# DRV8303.net
KiCad netlist of a schematic drawn in Altium Designer
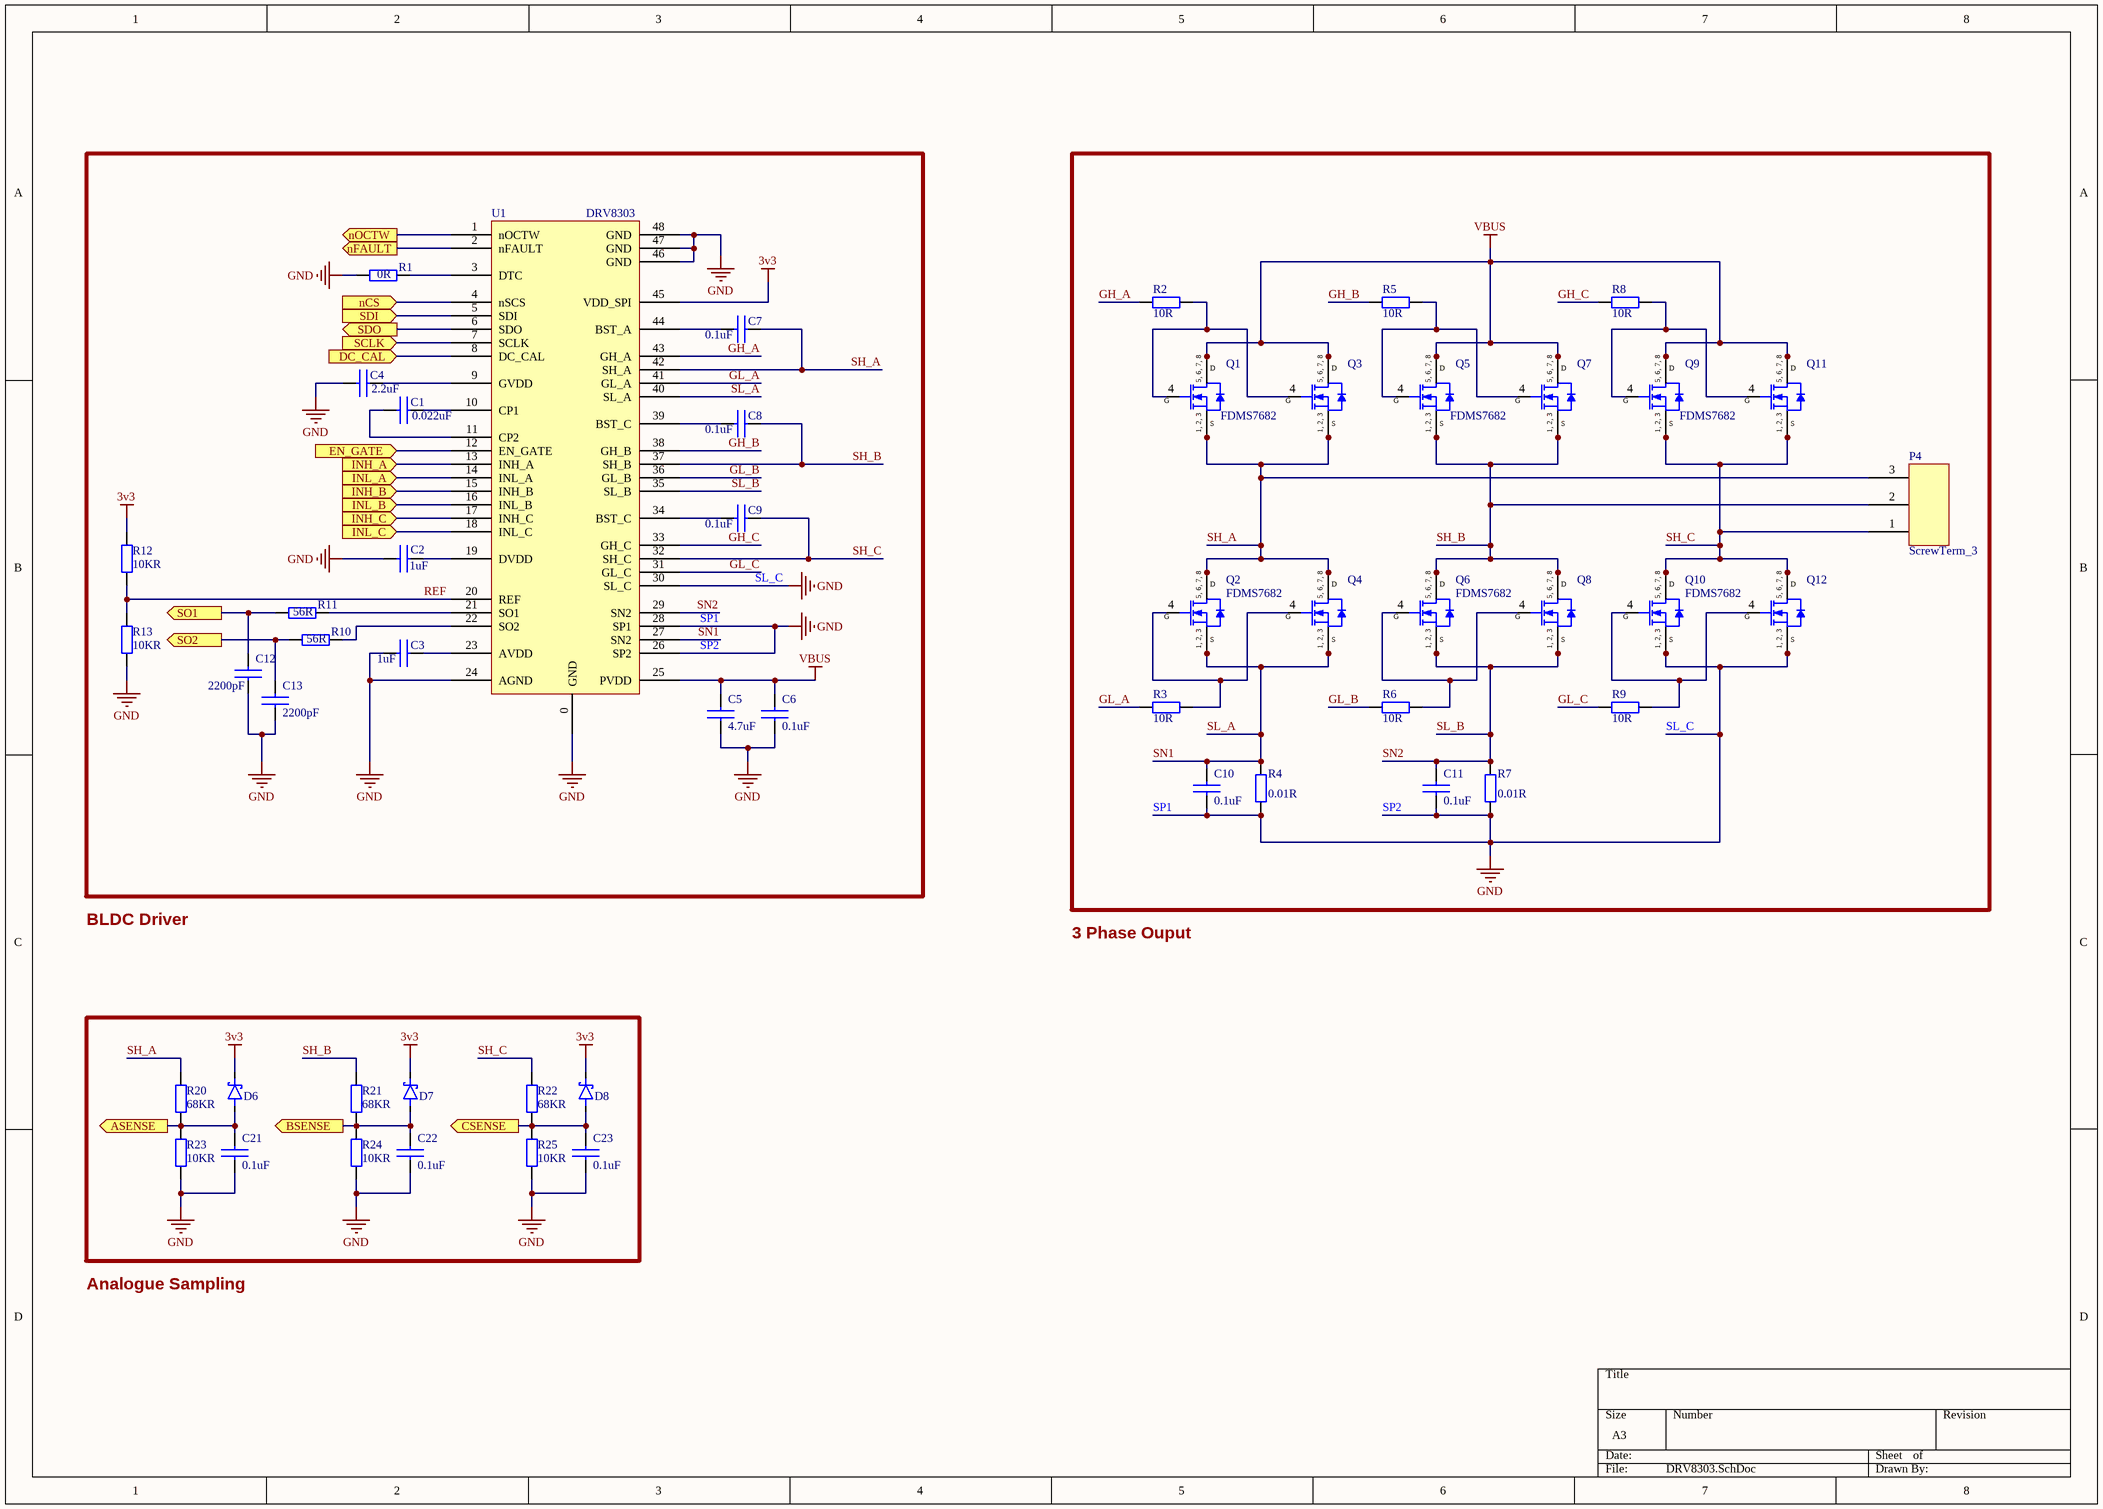
[diagram p0: DRV8303.SchDoc]

(export (version "E")
  (design (tool "Eeschema 10.0.6"))
  (components
    (comp (ref "C1")
      (value "0.022uF")
      (footprint "RESC0603(1608)_N")
      (description "Non polarized capacitor")
      (libsource (lib "myPassives") (part "Capacitor"))
    )
    (comp (ref "C2")
      (value "1uF")
      (footprint "RESC0603(1608)_N")
      (description "Non polarized capacitor")
      (libsource (lib "myPassives") (part "Capacitor"))
    )
    (comp (ref "C3")
      (value "1uF")
      (footprint "RESC0603(1608)_N")
      (description "Non polarized capacitor")
      (libsource (lib "myPassives") (part "Capacitor"))
    )
    (comp (ref "C4")
      (value "2.2uF")
      (footprint "RESC0603(1608)_N")
      (description "Non polarized capacitor")
      (libsource (lib "myPassives") (part "Capacitor"))
    )
    (comp (ref "C5")
      (value "4.7uF")
      (footprint "RESC0603(1608)_N")
      (description "Non polarized capacitor")
      (libsource (lib "myPassives") (part "Capacitor"))
    )
    (comp (ref "C6")
      (value "0.1uF")
      (footprint "RESC0603(1608)_N")
      (description "Non polarized capacitor")
      (libsource (lib "myPassives") (part "Capacitor"))
    )
    (comp (ref "C7")
      (value "0.1uF")
      (footprint "RESC0603(1608)_N")
      (description "Non polarized capacitor")
      (libsource (lib "myPassives") (part "Capacitor"))
    )
    (comp (ref "C8")
      (value "0.1uF")
      (footprint "RESC0603(1608)_N")
      (description "Non polarized capacitor")
      (libsource (lib "myPassives") (part "Capacitor"))
    )
    (comp (ref "C9")
      (value "0.1uF")
      (footprint "RESC0603(1608)_N")
      (description "Non polarized capacitor")
      (libsource (lib "myPassives") (part "Capacitor"))
    )
    (comp (ref "C10")
      (value "0.1uF")
      (footprint "RESC0603(1608)_N")
      (description "Non polarized capacitor")
      (libsource (lib "myPassives") (part "Capacitor"))
    )
    (comp (ref "C11")
      (value "0.1uF")
      (footprint "RESC0603(1608)_N")
      (description "Non polarized capacitor")
      (libsource (lib "myPassives") (part "Capacitor"))
    )
    (comp (ref "C12")
      (value "2200pF")
      (footprint "RESC0603(1608)_N")
      (description "Non polarized capacitor")
      (libsource (lib "myPassives") (part "Capacitor"))
    )
    (comp (ref "C13")
      (value "2200pF")
      (footprint "RESC0603(1608)_N")
      (description "Non polarized capacitor")
      (libsource (lib "myPassives") (part "Capacitor"))
    )
    (comp (ref "C21")
      (value "0.1uF")
      (footprint "RESC0603(1608)_N")
      (description "Non polarized capacitor")
      (libsource (lib "myPassives") (part "Capacitor"))
    )
    (comp (ref "C22")
      (value "0.1uF")
      (footprint "RESC0603(1608)_N")
      (description "Non polarized capacitor")
      (libsource (lib "myPassives") (part "Capacitor"))
    )
    (comp (ref "C23")
      (value "0.1uF")
      (footprint "RESC0603(1608)_N")
      (description "Non polarized capacitor")
      (libsource (lib "myPassives") (part "Capacitor"))
    )
    (comp (ref "D6")
      (value "Diode_schottky")
      (footprint "SOD523")
      (libsource (lib "myPassives") (part "Diode_schottky"))
    )
    (comp (ref "D7")
      (value "Diode_schottky")
      (footprint "SOD523")
      (libsource (lib "myPassives") (part "Diode_schottky"))
    )
    (comp (ref "D8")
      (value "Diode_schottky")
      (footprint "SOD523")
      (libsource (lib "myPassives") (part "Diode_schottky"))
    )
    (comp (ref "P4")
      (value "ScrewTerm_3")
      (footprint "ScrewTerm_3")
      (libsource (lib "Seeed") (part "ScrewTerm_3"))
    )
    (comp (ref "Q1") (value "FDMS7682") (footprint "PQFN8_5x6") (libsource (lib "myLibs") (part "FDMS7682")))
    (comp (ref "Q2") (value "FDMS7682") (footprint "PQFN8_5x6") (libsource (lib "myLibs") (part "FDMS7682")))
    (comp (ref "Q3") (value "FDMS7682") (footprint "PQFN8_5x6") (libsource (lib "myLibs") (part "FDMS7682")))
    (comp (ref "Q4") (value "FDMS7682") (footprint "PQFN8_5x6") (libsource (lib "myLibs") (part "FDMS7682")))
    (comp (ref "Q5") (value "FDMS7682") (footprint "PQFN8_5x6") (libsource (lib "myLibs") (part "FDMS7682")))
    (comp (ref "Q6") (value "FDMS7682") (footprint "PQFN8_5x6") (libsource (lib "myLibs") (part "FDMS7682")))
    (comp (ref "Q7") (value "FDMS7682") (footprint "PQFN8_5x6") (libsource (lib "myLibs") (part "FDMS7682")))
    (comp (ref "Q8") (value "FDMS7682") (footprint "PQFN8_5x6") (libsource (lib "myLibs") (part "FDMS7682")))
    (comp (ref "Q9") (value "FDMS7682") (footprint "PQFN8_5x6") (libsource (lib "myLibs") (part "FDMS7682")))
    (comp (ref "Q10") (value "FDMS7682") (footprint "PQFN8_5x6") (libsource (lib "myLibs") (part "FDMS7682")))
    (comp (ref "Q11") (value "FDMS7682") (footprint "PQFN8_5x6") (libsource (lib "myLibs") (part "FDMS7682")))
    (comp (ref "Q12") (value "FDMS7682") (footprint "PQFN8_5x6") (libsource (lib "myLibs") (part "FDMS7682")))
    (comp (ref "R1")
      (value "0R")
      (footprint "RESC0603(1608)_N")
      (description "Resistor")
      (libsource (lib "") (part "Resistor_2"))
    )
    (comp (ref "R2")
      (value "10R")
      (footprint "RESC0603(1608)_N")
      (description "Resistor")
      (libsource (lib "") (part "Resistor_2"))
    )
    (comp (ref "R3")
      (value "10R")
      (footprint "RESC0603(1608)_N")
      (description "Resistor")
      (libsource (lib "") (part "Resistor_2"))
    )
    (comp (ref "R4")
      (value "0.01R")
      (footprint "RESC1206(3216)_M")
      (description "Resistor")
      (libsource (lib "myPassives") (part "Resistor"))
    )
    (comp (ref "R5")
      (value "10R")
      (footprint "RESC0603(1608)_N")
      (description "Resistor")
      (libsource (lib "") (part "Resistor_2"))
    )
    (comp (ref "R6")
      (value "10R")
      (footprint "RESC0603(1608)_N")
      (description "Resistor")
      (libsource (lib "") (part "Resistor_2"))
    )
    (comp (ref "R7")
      (value "0.01R")
      (footprint "RESC1206(3216)_M")
      (description "Resistor")
      (libsource (lib "myPassives") (part "Resistor"))
    )
    (comp (ref "R8")
      (value "10R")
      (footprint "RESC0603(1608)_N")
      (description "Resistor")
      (libsource (lib "") (part "Resistor_2"))
    )
    (comp (ref "R9")
      (value "10R")
      (footprint "RESC0603(1608)_N")
      (description "Resistor")
      (libsource (lib "") (part "Resistor_2"))
    )
    (comp (ref "R10")
      (value "56R")
      (footprint "RESC0603(1608)_N")
      (description "Resistor")
      (libsource (lib "") (part "Resistor_2"))
    )
    (comp (ref "R11")
      (value "56R")
      (footprint "RESC0603(1608)_N")
      (description "Resistor")
      (libsource (lib "") (part "Resistor_2"))
    )
    (comp (ref "R12")
      (value "10KR")
      (footprint "RESC0603(1608)_N")
      (description "Resistor")
      (libsource (lib "") (part "Resistor_1"))
    )
    (comp (ref "R13")
      (value "10KR")
      (footprint "RESC0603(1608)_N")
      (description "Resistor")
      (libsource (lib "") (part "Resistor_1"))
    )
    (comp (ref "R20")
      (value "68KR")
      (footprint "RESC0603(1608)_N")
      (description "Resistor")
      (libsource (lib "") (part "Resistor_1"))
    )
    (comp (ref "R21")
      (value "68KR")
      (footprint "RESC0603(1608)_N")
      (description "Resistor")
      (libsource (lib "") (part "Resistor_1"))
    )
    (comp (ref "R22")
      (value "68KR")
      (footprint "RESC0603(1608)_N")
      (description "Resistor")
      (libsource (lib "") (part "Resistor_1"))
    )
    (comp (ref "R23")
      (value "10KR")
      (footprint "RESC0603(1608)_N")
      (description "Resistor")
      (libsource (lib "") (part "Resistor_1"))
    )
    (comp (ref "R24")
      (value "10KR")
      (footprint "RESC0603(1608)_N")
      (description "Resistor")
      (libsource (lib "") (part "Resistor_1"))
    )
    (comp (ref "R25")
      (value "10KR")
      (footprint "RESC0603(1608)_N")
      (description "Resistor")
      (libsource (lib "") (part "Resistor_1"))
    )
    (comp (ref "U1") (value "DRV8303") (footprint "HSSOP48") (libsource (lib "myLibs") (part "DRV8303")))
  )
  (nets
    (net (code "1") (name "/ASENSE") (class "Default")
      (node (ref "C21") (pin "1") (pintype "passive"))
      (node (ref "D6") (pin "2") (pintype "passive"))
      (node (ref "R20") (pin "1") (pintype "passive"))
      (node (ref "R23") (pin "2") (pintype "passive"))
    )
    (net (code "2") (name "/BSENSE") (class "Default")
      (node (ref "C22") (pin "1") (pintype "passive"))
      (node (ref "D7") (pin "2") (pintype "passive"))
      (node (ref "R21") (pin "1") (pintype "passive"))
      (node (ref "R24") (pin "2") (pintype "passive"))
    )
    (net (code "3") (name "/CSENSE") (class "Default")
      (node (ref "C23") (pin "1") (pintype "passive"))
      (node (ref "D8") (pin "2") (pintype "passive"))
      (node (ref "R22") (pin "1") (pintype "passive"))
      (node (ref "R25") (pin "2") (pintype "passive"))
    )
    (net (code "4") (name "/DC_CAL") (class "Default")
      (node (ref "U1") (pin "8") (pinfunction "DC_CAL_8") (pintype "passive"))
    )
    (net (code "5") (name "/EN_GATE") (class "Default")
      (node (ref "U1") (pin "12") (pinfunction "EN_GATE_12") (pintype "passive"))
    )
    (net (code "6") (name "/GH_A") (class "Default")
      (node (ref "R2") (pin "1") (pintype "passive"))
      (node (ref "U1") (pin "43") (pinfunction "GH_A_43") (pintype "passive"))
    )
    (net (code "7") (name "/GH_B") (class "Default")
      (node (ref "R5") (pin "1") (pintype "passive"))
      (node (ref "U1") (pin "38") (pinfunction "GH_B_38") (pintype "passive"))
    )
    (net (code "8") (name "/GH_C") (class "Default")
      (node (ref "R8") (pin "1") (pintype "passive"))
      (node (ref "U1") (pin "33") (pinfunction "GH_C_33") (pintype "passive"))
    )
    (net (code "9") (name "/GL_A") (class "Default")
      (node (ref "R3") (pin "1") (pintype "passive"))
      (node (ref "U1") (pin "41") (pinfunction "GL_A_41") (pintype "passive"))
    )
    (net (code "10") (name "/GL_B") (class "Default")
      (node (ref "R6") (pin "1") (pintype "passive"))
      (node (ref "U1") (pin "36") (pinfunction "GL_B_36") (pintype "passive"))
    )
    (net (code "11") (name "/GL_C") (class "Default")
      (node (ref "R9") (pin "1") (pintype "passive"))
      (node (ref "U1") (pin "31") (pinfunction "GL_C_31") (pintype "passive"))
    )
    (net (code "12") (name "/INH_A") (class "Default")
      (node (ref "U1") (pin "13") (pinfunction "INH_A_13") (pintype "passive"))
    )
    (net (code "13") (name "/INH_B") (class "Default")
      (node (ref "U1") (pin "15") (pinfunction "INH_B_15") (pintype "passive"))
    )
    (net (code "14") (name "/INH_C") (class "Default")
      (node (ref "U1") (pin "17") (pinfunction "INH_C_17") (pintype "passive"))
    )
    (net (code "15") (name "/INL_A") (class "Default")
      (node (ref "U1") (pin "14") (pinfunction "INL_A_14") (pintype "passive"))
    )
    (net (code "16") (name "/INL_B") (class "Default")
      (node (ref "U1") (pin "16") (pinfunction "INL_B_16") (pintype "passive"))
    )
    (net (code "17") (name "/INL_C") (class "Default")
      (node (ref "U1") (pin "18") (pinfunction "INL_C_18") (pintype "passive"))
    )
    (net (code "18") (name "/REF") (class "Default")
      (node (ref "R12") (pin "1") (pintype "passive"))
      (node (ref "R13") (pin "2") (pintype "passive"))
      (node (ref "U1") (pin "20") (pinfunction "REF_20") (pintype "passive"))
    )
    (net (code "19") (name "/SCLK") (class "Default")
      (node (ref "U1") (pin "7") (pinfunction "SCLK_7") (pintype "passive"))
    )
    (net (code "20") (name "/SDI") (class "Default")
      (node (ref "U1") (pin "5") (pinfunction "SDI_5") (pintype "passive"))
    )
    (net (code "21") (name "/SDO") (class "Default")
      (node (ref "U1") (pin "6") (pinfunction "SDO_6") (pintype "passive"))
    )
    (net (code "22") (name "/SH_A") (class "Default")
      (node (ref "C7") (pin "2") (pintype "passive"))
      (node (ref "P4") (pin "3") (pintype "passive"))
      (node (ref "Q1") (pin "1") (pinfunction "S_1") (pintype "passive"))
      (node (ref "Q1") (pin "2") (pinfunction "S_2") (pintype "power_in"))
      (node (ref "Q1") (pin "3") (pinfunction "S_3") (pintype "power_in"))
      (node (ref "Q2") (pin "0") (pinfunction "D_0") (pintype "passive"))
      (node (ref "Q2") (pin "5") (pinfunction "D_5") (pintype "passive"))
      (node (ref "Q2") (pin "6") (pinfunction "D_6") (pintype "passive"))
      (node (ref "Q2") (pin "7") (pinfunction "D_7") (pintype "passive"))
      (node (ref "Q2") (pin "8") (pinfunction "D_8") (pintype "passive"))
      (node (ref "Q3") (pin "1") (pinfunction "S_1") (pintype "passive"))
      (node (ref "Q3") (pin "2") (pinfunction "S_2") (pintype "power_in"))
      (node (ref "Q3") (pin "3") (pinfunction "S_3") (pintype "power_in"))
      (node (ref "Q4") (pin "0") (pinfunction "D_0") (pintype "passive"))
      (node (ref "Q4") (pin "5") (pinfunction "D_5") (pintype "passive"))
      (node (ref "Q4") (pin "6") (pinfunction "D_6") (pintype "passive"))
      (node (ref "Q4") (pin "7") (pinfunction "D_7") (pintype "passive"))
      (node (ref "Q4") (pin "8") (pinfunction "D_8") (pintype "passive"))
      (node (ref "R20") (pin "2") (pintype "passive"))
      (node (ref "U1") (pin "42") (pinfunction "SH_A_42") (pintype "passive"))
    )
    (net (code "23") (name "/SH_B") (class "Default")
      (node (ref "C8") (pin "2") (pintype "passive"))
      (node (ref "P4") (pin "2") (pintype "passive"))
      (node (ref "Q5") (pin "1") (pinfunction "S_1") (pintype "passive"))
      (node (ref "Q5") (pin "2") (pinfunction "S_2") (pintype "power_in"))
      (node (ref "Q5") (pin "3") (pinfunction "S_3") (pintype "power_in"))
      (node (ref "Q6") (pin "0") (pinfunction "D_0") (pintype "passive"))
      (node (ref "Q6") (pin "5") (pinfunction "D_5") (pintype "passive"))
      (node (ref "Q6") (pin "6") (pinfunction "D_6") (pintype "passive"))
      (node (ref "Q6") (pin "7") (pinfunction "D_7") (pintype "passive"))
      (node (ref "Q6") (pin "8") (pinfunction "D_8") (pintype "passive"))
      (node (ref "Q7") (pin "1") (pinfunction "S_1") (pintype "passive"))
      (node (ref "Q7") (pin "2") (pinfunction "S_2") (pintype "power_in"))
      (node (ref "Q7") (pin "3") (pinfunction "S_3") (pintype "power_in"))
      (node (ref "Q8") (pin "0") (pinfunction "D_0") (pintype "passive"))
      (node (ref "Q8") (pin "5") (pinfunction "D_5") (pintype "passive"))
      (node (ref "Q8") (pin "6") (pinfunction "D_6") (pintype "passive"))
      (node (ref "Q8") (pin "7") (pinfunction "D_7") (pintype "passive"))
      (node (ref "Q8") (pin "8") (pinfunction "D_8") (pintype "passive"))
      (node (ref "R21") (pin "2") (pintype "passive"))
      (node (ref "U1") (pin "37") (pinfunction "SH_B_37") (pintype "passive"))
    )
    (net (code "24") (name "/SH_C") (class "Default")
      (node (ref "C9") (pin "2") (pintype "passive"))
      (node (ref "P4") (pin "1") (pintype "passive"))
      (node (ref "Q10") (pin "0") (pinfunction "D_0") (pintype "passive"))
      (node (ref "Q10") (pin "5") (pinfunction "D_5") (pintype "passive"))
      (node (ref "Q10") (pin "6") (pinfunction "D_6") (pintype "passive"))
      (node (ref "Q10") (pin "7") (pinfunction "D_7") (pintype "passive"))
      (node (ref "Q10") (pin "8") (pinfunction "D_8") (pintype "passive"))
      (node (ref "Q11") (pin "1") (pinfunction "S_1") (pintype "passive"))
      (node (ref "Q11") (pin "2") (pinfunction "S_2") (pintype "power_in"))
      (node (ref "Q11") (pin "3") (pinfunction "S_3") (pintype "power_in"))
      (node (ref "Q12") (pin "0") (pinfunction "D_0") (pintype "passive"))
      (node (ref "Q12") (pin "5") (pinfunction "D_5") (pintype "passive"))
      (node (ref "Q12") (pin "6") (pinfunction "D_6") (pintype "passive"))
      (node (ref "Q12") (pin "7") (pinfunction "D_7") (pintype "passive"))
      (node (ref "Q12") (pin "8") (pinfunction "D_8") (pintype "passive"))
      (node (ref "Q9") (pin "1") (pinfunction "S_1") (pintype "passive"))
      (node (ref "Q9") (pin "2") (pinfunction "S_2") (pintype "power_in"))
      (node (ref "Q9") (pin "3") (pinfunction "S_3") (pintype "power_in"))
      (node (ref "R22") (pin "2") (pintype "passive"))
      (node (ref "U1") (pin "32") (pinfunction "SH_C_32") (pintype "passive"))
    )
    (net (code "25") (name "/SL_A") (class "Default")
      (node (ref "C10") (pin "1") (pintype "passive"))
      (node (ref "Q2") (pin "1") (pinfunction "S_1") (pintype "passive"))
      (node (ref "Q2") (pin "2") (pinfunction "S_2") (pintype "power_in"))
      (node (ref "Q2") (pin "3") (pinfunction "S_3") (pintype "power_in"))
      (node (ref "Q4") (pin "1") (pinfunction "S_1") (pintype "passive"))
      (node (ref "Q4") (pin "2") (pinfunction "S_2") (pintype "power_in"))
      (node (ref "Q4") (pin "3") (pinfunction "S_3") (pintype "power_in"))
      (node (ref "R4") (pin "1") (pintype "passive"))
      (node (ref "U1") (pin "27") (pinfunction "SN2_27") (pintype "passive"))
      (node (ref "U1") (pin "40") (pinfunction "SL_A_40") (pintype "passive"))
    )
    (net (code "26") (name "/SL_B") (class "Default")
      (node (ref "C11") (pin "1") (pintype "passive"))
      (node (ref "Q6") (pin "1") (pinfunction "S_1") (pintype "passive"))
      (node (ref "Q6") (pin "2") (pinfunction "S_2") (pintype "power_in"))
      (node (ref "Q6") (pin "3") (pinfunction "S_3") (pintype "power_in"))
      (node (ref "Q8") (pin "1") (pinfunction "S_1") (pintype "passive"))
      (node (ref "Q8") (pin "2") (pinfunction "S_2") (pintype "power_in"))
      (node (ref "Q8") (pin "3") (pinfunction "S_3") (pintype "power_in"))
      (node (ref "R7") (pin "1") (pintype "passive"))
      (node (ref "U1") (pin "29") (pinfunction "SN2_29") (pintype "passive"))
      (node (ref "U1") (pin "35") (pinfunction "SL_B_35") (pintype "passive"))
    )
    (net (code "27") (name "/SO1") (class "Default")
      (node (ref "C12") (pin "1") (pintype "passive"))
      (node (ref "R11") (pin "1") (pintype "passive"))
    )
    (net (code "28") (name "/SO2") (class "Default")
      (node (ref "C13") (pin "1") (pintype "passive"))
      (node (ref "R10") (pin "1") (pintype "passive"))
    )
    (net (code "29") (name "/nCS") (class "Default")
      (node (ref "U1") (pin "4") (pinfunction "nSCS_4") (pintype "passive"))
    )
    (net (code "30") (name "/nFAULT") (class "Default")
      (node (ref "U1") (pin "2") (pinfunction "nFAULT_2") (pintype "passive"))
    )
    (net (code "31") (name "/nOCTW") (class "Default")
      (node (ref "U1") (pin "1") (pinfunction "nOCTW_1") (pintype "passive"))
    )
    (net (code "32") (name "3v3") (class "Default")
      (node (ref "D6") (pin "1") (pintype "passive"))
      (node (ref "D7") (pin "1") (pintype "passive"))
      (node (ref "D8") (pin "1") (pintype "passive"))
      (node (ref "R12") (pin "2") (pintype "passive"))
      (node (ref "U1") (pin "45") (pinfunction "VDD_SPI_45") (pintype "passive"))
    )
    (net (code "33") (name "GND") (class "Default")
      (node (ref "C10") (pin "2") (pintype "passive"))
      (node (ref "C11") (pin "2") (pintype "passive"))
      (node (ref "C12") (pin "2") (pintype "passive"))
      (node (ref "C13") (pin "2") (pintype "passive"))
      (node (ref "C2") (pin "1") (pintype "passive"))
      (node (ref "C21") (pin "2") (pintype "passive"))
      (node (ref "C22") (pin "2") (pintype "passive"))
      (node (ref "C23") (pin "2") (pintype "passive"))
      (node (ref "C3") (pin "1") (pintype "passive"))
      (node (ref "C4") (pin "1") (pintype "passive"))
      (node (ref "C5") (pin "2") (pintype "passive"))
      (node (ref "C6") (pin "2") (pintype "passive"))
      (node (ref "Q10") (pin "1") (pinfunction "S_1") (pintype "passive"))
      (node (ref "Q10") (pin "2") (pinfunction "S_2") (pintype "power_in"))
      (node (ref "Q10") (pin "3") (pinfunction "S_3") (pintype "power_in"))
      (node (ref "Q12") (pin "1") (pinfunction "S_1") (pintype "passive"))
      (node (ref "Q12") (pin "2") (pinfunction "S_2") (pintype "power_in"))
      (node (ref "Q12") (pin "3") (pinfunction "S_3") (pintype "power_in"))
      (node (ref "R1") (pin "1") (pintype "passive"))
      (node (ref "R13") (pin "1") (pintype "passive"))
      (node (ref "R23") (pin "1") (pintype "passive"))
      (node (ref "R24") (pin "1") (pintype "passive"))
      (node (ref "R25") (pin "1") (pintype "passive"))
      (node (ref "R4") (pin "2") (pintype "passive"))
      (node (ref "R7") (pin "2") (pintype "passive"))
      (node (ref "U1") (pin "0") (pinfunction "GND_0") (pintype "passive"))
      (node (ref "U1") (pin "24") (pinfunction "AGND_24") (pintype "passive"))
      (node (ref "U1") (pin "26") (pinfunction "SP2_26") (pintype "passive"))
      (node (ref "U1") (pin "28") (pinfunction "SP1_28") (pintype "passive"))
      (node (ref "U1") (pin "30") (pinfunction "SL_C_30") (pintype "passive"))
      (node (ref "U1") (pin "46") (pinfunction "GND_46") (pintype "passive"))
      (node (ref "U1") (pin "47") (pinfunction "GND_47") (pintype "passive"))
      (node (ref "U1") (pin "48") (pinfunction "GND_48") (pintype "passive"))
    )
    (net (code "34") (name "Net-(C8-Pad1)") (class "Default")
      (node (ref "C8") (pin "1") (pintype "passive"))
      (node (ref "U1") (pin "39") (pinfunction "BST_C_39") (pintype "passive"))
    )
    (net (code "35") (name "Net-(C9-Pad1)") (class "Default")
      (node (ref "C9") (pin "1") (pintype "passive"))
      (node (ref "U1") (pin "34") (pinfunction "BST_C_34") (pintype "passive"))
    )
    (net (code "36") (name "Net-(Q1-G)") (class "Default")
      (node (ref "Q1") (pin "4") (pinfunction "G_4") (pintype "passive"))
      (node (ref "Q3") (pin "4") (pinfunction "G_4") (pintype "passive"))
      (node (ref "R2") (pin "2") (pintype "passive"))
    )
    (net (code "37") (name "Net-(Q2-G)") (class "Default")
      (node (ref "Q2") (pin "4") (pinfunction "G_4") (pintype "passive"))
      (node (ref "Q4") (pin "4") (pinfunction "G_4") (pintype "passive"))
      (node (ref "R3") (pin "2") (pintype "passive"))
    )
    (net (code "38") (name "Net-(Q5-G)") (class "Default")
      (node (ref "Q5") (pin "4") (pinfunction "G_4") (pintype "passive"))
      (node (ref "Q7") (pin "4") (pinfunction "G_4") (pintype "passive"))
      (node (ref "R5") (pin "2") (pintype "passive"))
    )
    (net (code "39") (name "Net-(Q6-G)") (class "Default")
      (node (ref "Q6") (pin "4") (pinfunction "G_4") (pintype "passive"))
      (node (ref "Q8") (pin "4") (pinfunction "G_4") (pintype "passive"))
      (node (ref "R6") (pin "2") (pintype "passive"))
    )
    (net (code "40") (name "Net-(Q10-G)") (class "Default")
      (node (ref "Q10") (pin "4") (pinfunction "G_4") (pintype "passive"))
      (node (ref "Q12") (pin "4") (pinfunction "G_4") (pintype "passive"))
      (node (ref "R9") (pin "2") (pintype "passive"))
    )
    (net (code "41") (name "Net-(Q11-G)") (class "Default")
      (node (ref "Q11") (pin "4") (pinfunction "G_4") (pintype "passive"))
      (node (ref "Q9") (pin "4") (pinfunction "G_4") (pintype "passive"))
      (node (ref "R8") (pin "2") (pintype "passive"))
    )
    (net (code "42") (name "Net-(U1-AVDD)") (class "Default")
      (node (ref "C3") (pin "2") (pintype "passive"))
      (node (ref "U1") (pin "23") (pinfunction "AVDD_23") (pintype "passive"))
    )
    (net (code "43") (name "Net-(U1-BST_A)") (class "Default")
      (node (ref "C7") (pin "1") (pintype "passive"))
      (node (ref "U1") (pin "44") (pinfunction "BST_A_44") (pintype "passive"))
    )
    (net (code "44") (name "Net-(U1-CP1)") (class "Default")
      (node (ref "C1") (pin "2") (pintype "passive"))
      (node (ref "U1") (pin "10") (pinfunction "CP1_10") (pintype "passive"))
    )
    (net (code "45") (name "Net-(U1-CP2)") (class "Default")
      (node (ref "C1") (pin "1") (pintype "passive"))
      (node (ref "U1") (pin "11") (pinfunction "CP2_11") (pintype "passive"))
    )
    (net (code "46") (name "Net-(U1-DTC)") (class "Default")
      (node (ref "R1") (pin "2") (pintype "passive"))
      (node (ref "U1") (pin "3") (pinfunction "DTC_3") (pintype "passive"))
    )
    (net (code "47") (name "Net-(U1-DVDD)") (class "Default")
      (node (ref "C2") (pin "2") (pintype "passive"))
      (node (ref "U1") (pin "19") (pinfunction "DVDD_19") (pintype "passive"))
    )
    (net (code "48") (name "Net-(U1-GVDD)") (class "Default")
      (node (ref "C4") (pin "2") (pintype "passive"))
      (node (ref "U1") (pin "9") (pinfunction "GVDD_9") (pintype "passive"))
    )
    (net (code "49") (name "Net-(U1-SO1)") (class "Default")
      (node (ref "R11") (pin "2") (pintype "passive"))
      (node (ref "U1") (pin "21") (pinfunction "SO1_21") (pintype "passive"))
    )
    (net (code "50") (name "Net-(U1-SO2)") (class "Default")
      (node (ref "R10") (pin "2") (pintype "passive"))
      (node (ref "U1") (pin "22") (pinfunction "SO2_22") (pintype "passive"))
    )
    (net (code "51") (name "VBUS") (class "Default")
      (node (ref "C5") (pin "1") (pintype "passive"))
      (node (ref "C6") (pin "1") (pintype "passive"))
      (node (ref "Q1") (pin "0") (pinfunction "D_0") (pintype "passive"))
      (node (ref "Q1") (pin "5") (pinfunction "D_5") (pintype "passive"))
      (node (ref "Q1") (pin "6") (pinfunction "D_6") (pintype "passive"))
      (node (ref "Q1") (pin "7") (pinfunction "D_7") (pintype "passive"))
      (node (ref "Q1") (pin "8") (pinfunction "D_8") (pintype "passive"))
      (node (ref "Q11") (pin "0") (pinfunction "D_0") (pintype "passive"))
      (node (ref "Q11") (pin "5") (pinfunction "D_5") (pintype "passive"))
      (node (ref "Q11") (pin "6") (pinfunction "D_6") (pintype "passive"))
      (node (ref "Q11") (pin "7") (pinfunction "D_7") (pintype "passive"))
      (node (ref "Q11") (pin "8") (pinfunction "D_8") (pintype "passive"))
      (node (ref "Q3") (pin "0") (pinfunction "D_0") (pintype "passive"))
      (node (ref "Q3") (pin "5") (pinfunction "D_5") (pintype "passive"))
      (node (ref "Q3") (pin "6") (pinfunction "D_6") (pintype "passive"))
      (node (ref "Q3") (pin "7") (pinfunction "D_7") (pintype "passive"))
      (node (ref "Q3") (pin "8") (pinfunction "D_8") (pintype "passive"))
      (node (ref "Q5") (pin "0") (pinfunction "D_0") (pintype "passive"))
      (node (ref "Q5") (pin "5") (pinfunction "D_5") (pintype "passive"))
      (node (ref "Q5") (pin "6") (pinfunction "D_6") (pintype "passive"))
      (node (ref "Q5") (pin "7") (pinfunction "D_7") (pintype "passive"))
      (node (ref "Q5") (pin "8") (pinfunction "D_8") (pintype "passive"))
      (node (ref "Q7") (pin "0") (pinfunction "D_0") (pintype "passive"))
      (node (ref "Q7") (pin "5") (pinfunction "D_5") (pintype "passive"))
      (node (ref "Q7") (pin "6") (pinfunction "D_6") (pintype "passive"))
      (node (ref "Q7") (pin "7") (pinfunction "D_7") (pintype "passive"))
      (node (ref "Q7") (pin "8") (pinfunction "D_8") (pintype "passive"))
      (node (ref "Q9") (pin "0") (pinfunction "D_0") (pintype "passive"))
      (node (ref "Q9") (pin "5") (pinfunction "D_5") (pintype "passive"))
      (node (ref "Q9") (pin "6") (pinfunction "D_6") (pintype "passive"))
      (node (ref "Q9") (pin "7") (pinfunction "D_7") (pintype "passive"))
      (node (ref "Q9") (pin "8") (pinfunction "D_8") (pintype "passive"))
      (node (ref "U1") (pin "25") (pinfunction "PVDD_25") (pintype "passive"))
    )
  )
)
